# MucDuino_Strawberry.net
KiCad netlist of a schematic drawn in EAGLE
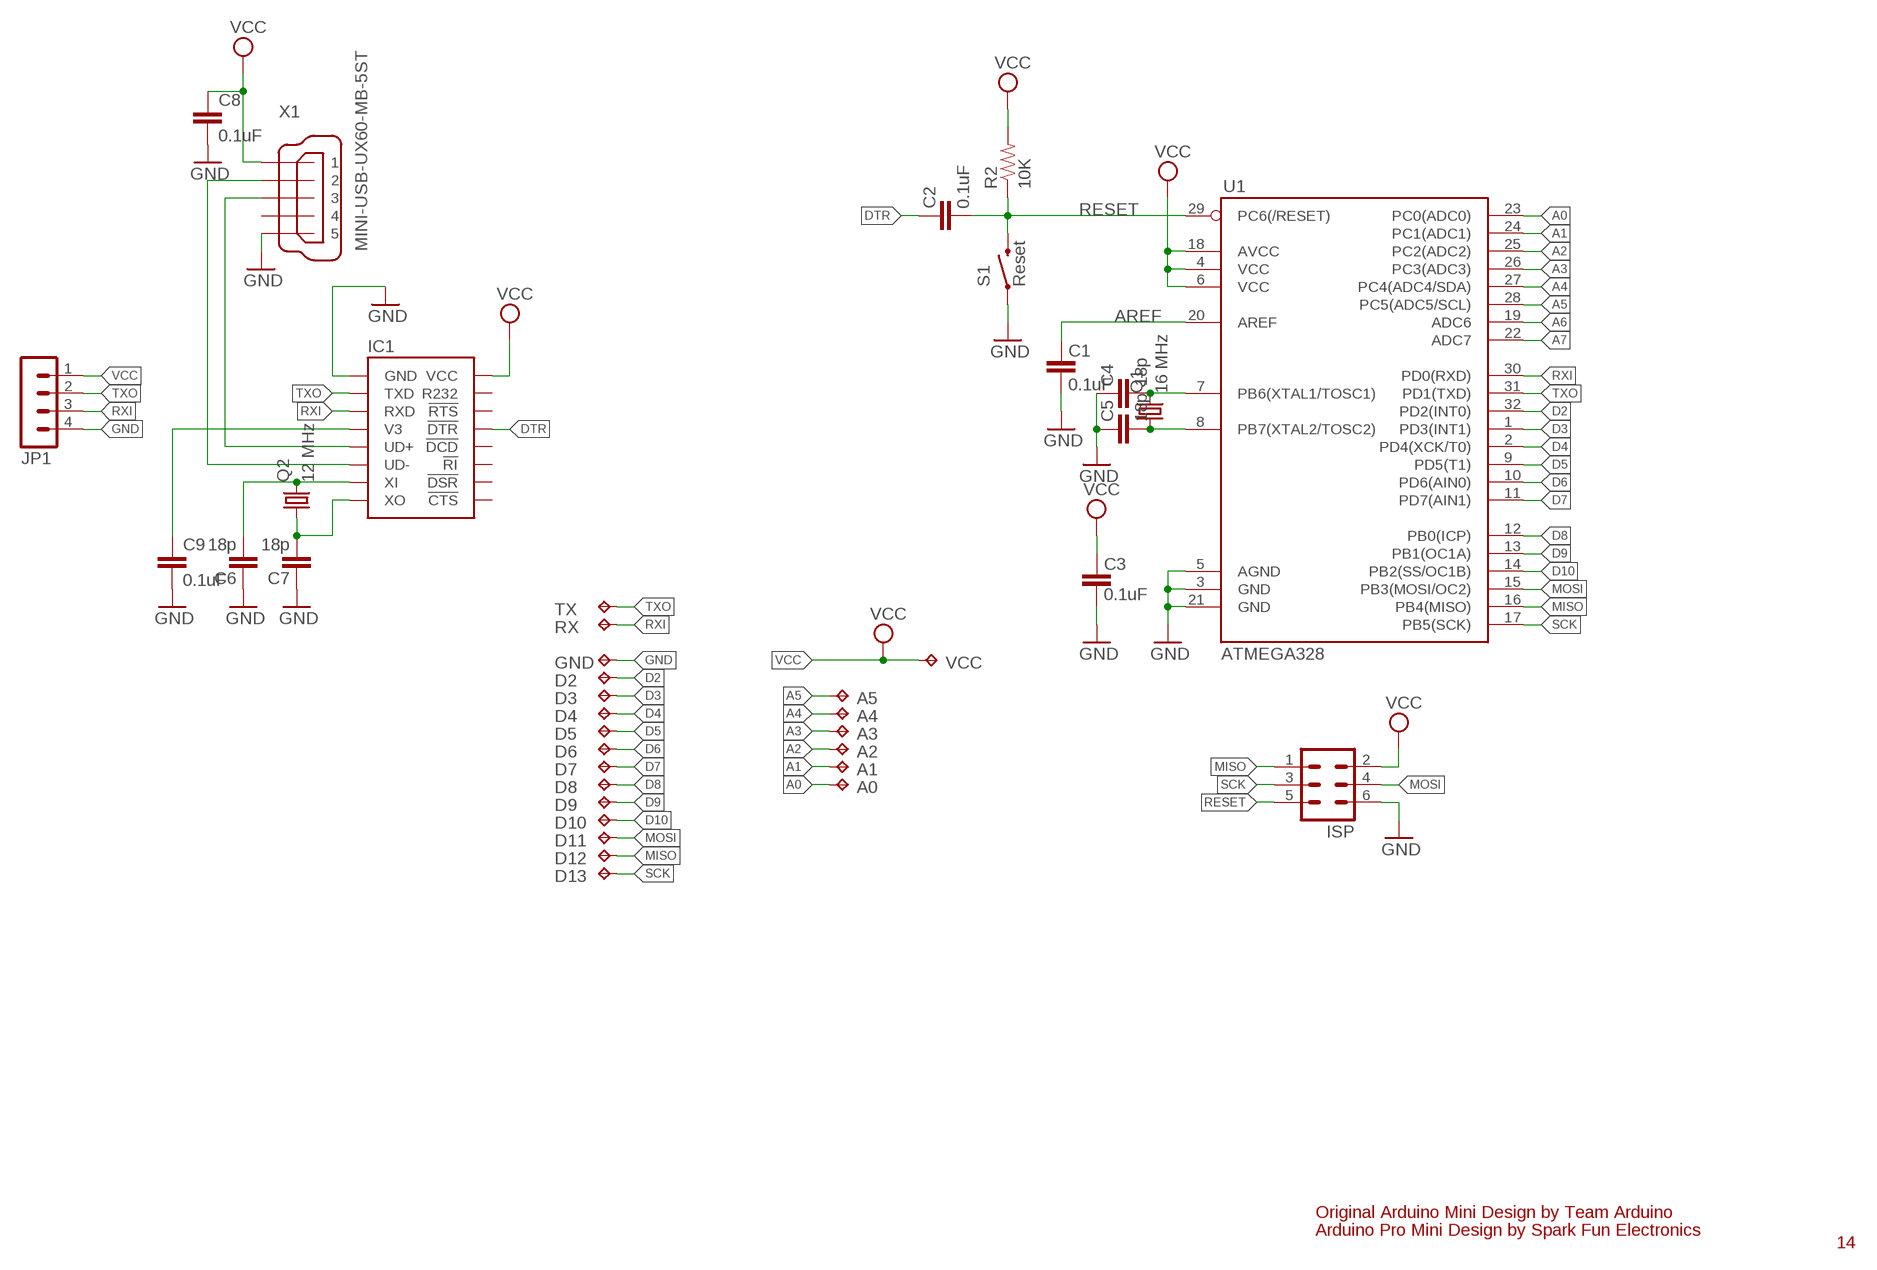
[diagram p0: schematic, sheet 1]

(export (version "E")
  (design (tool "Eeschema 10.0.6"))
  (components
    (comp (ref "A0")
      (value "TPPAD1-13")
      (footprint "eagle-import:P1-13")
      (libsource (lib "eagle-import") (part "TPPAD1-13"))
    )
    (comp (ref "A1")
      (value "TPPAD1-13")
      (footprint "eagle-import:P1-13")
      (libsource (lib "eagle-import") (part "TPPAD1-13"))
    )
    (comp (ref "A2")
      (value "TPPAD1-13")
      (footprint "eagle-import:P1-13")
      (libsource (lib "eagle-import") (part "TPPAD1-13"))
    )
    (comp (ref "A3")
      (value "TPPAD1-13")
      (footprint "eagle-import:P1-13")
      (libsource (lib "eagle-import") (part "TPPAD1-13"))
    )
    (comp (ref "A4")
      (value "TPPAD1-13")
      (footprint "eagle-import:P1-13")
      (libsource (lib "eagle-import") (part "TPPAD1-13"))
    )
    (comp (ref "A5")
      (value "TPPAD1-13")
      (footprint "eagle-import:P1-13")
      (libsource (lib "eagle-import") (part "TPPAD1-13"))
    )
    (comp (ref "C1")
      (value "0.1uF")
      (footprint "eagle-import:0603-CAP")
      (libsource (lib "eagle-import") (part "CAP0603-CAP"))
    )
    (comp (ref "C2")
      (value "0.1uF")
      (footprint "eagle-import:0603-CAP")
      (libsource (lib "eagle-import") (part "CAP0603-CAP"))
    )
    (comp (ref "C3")
      (value "0.1uF")
      (footprint "eagle-import:0603-CAP")
      (libsource (lib "eagle-import") (part "CAP0603-CAP"))
    )
    (comp (ref "C4")
      (value "18p")
      (footprint "eagle-import:0603-CAP")
      (libsource (lib "eagle-import") (part "CAP0603-CAP"))
    )
    (comp (ref "C5")
      (value "18p")
      (footprint "eagle-import:0603-CAP")
      (libsource (lib "eagle-import") (part "CAP0603-CAP"))
    )
    (comp (ref "C6")
      (value "18p")
      (footprint "eagle-import:0603-CAP")
      (libsource (lib "eagle-import") (part "CAP0603-CAP"))
    )
    (comp (ref "C7")
      (value "18p")
      (footprint "eagle-import:0603-CAP")
      (libsource (lib "eagle-import") (part "CAP0603-CAP"))
    )
    (comp (ref "C8")
      (value "0.1uF")
      (footprint "eagle-import:0603-CAP")
      (libsource (lib "eagle-import") (part "CAP0603-CAP"))
    )
    (comp (ref "C9")
      (value "0.1uF")
      (footprint "eagle-import:0603-CAP")
      (libsource (lib "eagle-import") (part "CAP0603-CAP"))
    )
    (comp (ref "D2")
      (value "TPPAD1-13")
      (footprint "eagle-import:P1-13")
      (libsource (lib "eagle-import") (part "TPPAD1-13"))
    )
    (comp (ref "D3")
      (value "TPPAD1-13")
      (footprint "eagle-import:P1-13")
      (libsource (lib "eagle-import") (part "TPPAD1-13"))
    )
    (comp (ref "D4")
      (value "TPPAD1-13")
      (footprint "eagle-import:P1-13")
      (libsource (lib "eagle-import") (part "TPPAD1-13"))
    )
    (comp (ref "D5")
      (value "TPPAD1-13")
      (footprint "eagle-import:P1-13")
      (libsource (lib "eagle-import") (part "TPPAD1-13"))
    )
    (comp (ref "D6")
      (value "TPPAD1-13")
      (footprint "eagle-import:P1-13")
      (libsource (lib "eagle-import") (part "TPPAD1-13"))
    )
    (comp (ref "D7")
      (value "TPPAD1-13")
      (footprint "eagle-import:P1-13")
      (libsource (lib "eagle-import") (part "TPPAD1-13"))
    )
    (comp (ref "D8")
      (value "TPPAD1-13")
      (footprint "eagle-import:P1-13")
      (libsource (lib "eagle-import") (part "TPPAD1-13"))
    )
    (comp (ref "D9")
      (value "TPPAD1-13")
      (footprint "eagle-import:P1-13")
      (libsource (lib "eagle-import") (part "TPPAD1-13"))
    )
    (comp (ref "D10")
      (value "TPPAD1-13")
      (footprint "eagle-import:P1-13")
      (libsource (lib "eagle-import") (part "TPPAD1-13"))
    )
    (comp (ref "D11")
      (value "TPPAD1-13")
      (footprint "eagle-import:P1-13")
      (libsource (lib "eagle-import") (part "TPPAD1-13"))
    )
    (comp (ref "D12")
      (value "TPPAD1-13")
      (footprint "eagle-import:P1-13")
      (libsource (lib "eagle-import") (part "TPPAD1-13"))
    )
    (comp (ref "D13")
      (value "TPPAD1-13")
      (footprint "eagle-import:P1-13")
      (libsource (lib "eagle-import") (part "TPPAD1-13"))
    )
    (comp (ref "GND")
      (value "TPPAD1-13")
      (footprint "eagle-import:P1-13")
      (libsource (lib "eagle-import") (part "TPPAD1-13"))
    )
    (comp (ref "IC1")
      (value "CH340G")
      (footprint "eagle-import:SOP16-209MM")
      (libsource (lib "eagle-import") (part "CH340G"))
    )
    (comp (ref "ISP")
      (value "MA03-2")
      (footprint "eagle-import:MA03-2")
      (libsource (lib "eagle-import") (part "MA03-2"))
    )
    (comp (ref "JP1")
      (value "MA04-1")
      (footprint "eagle-import:MA04-1")
      (libsource (lib "eagle-import") (part "MA04-1"))
    )
    (comp (ref "Q1")
      (value "16 MHz")
      (footprint "eagle-import:HC49UP")
      (libsource (lib "eagle-import") (part "CRYSTALHC49UP"))
    )
    (comp (ref "Q2")
      (value "12 MHz")
      (footprint "eagle-import:HC49UP")
      (libsource (lib "eagle-import") (part "CRYSTALHC49UP"))
    )
    (comp (ref "R2")
      (value "10K")
      (footprint "eagle-import:0603-RES")
      (libsource (lib "eagle-import") (part "RESISTOR0603-RES"))
    )
    (comp (ref "RX")
      (value "TPPAD1-13")
      (footprint "eagle-import:P1-13")
      (libsource (lib "eagle-import") (part "TPPAD1-13"))
    )
    (comp (ref "S1")
      (value "Reset")
      (footprint "eagle-import:TACTILE-SWITCH-SMD-ALT01")
      (libsource (lib "eagle-import") (part "SWITCH-MOMENTARY-2SMD-ALT01"))
    )
    (comp (ref "TX")
      (value "TPPAD1-13")
      (footprint "eagle-import:P1-13")
      (libsource (lib "eagle-import") (part "TPPAD1-13"))
    )
    (comp (ref "U1")
      (value "ATMEGA328")
      (footprint "eagle-import:TQFP32-08")
      (libsource (lib "eagle-import") (part "ATMEGA168"))
    )
    (comp (ref "VCC")
      (value "TPPAD1-13")
      (footprint "eagle-import:P1-13")
      (libsource (lib "eagle-import") (part "TPPAD1-13"))
    )
    (comp (ref "X1")
      (value "MINI-USB-UX60-MB-5ST")
      (footprint "eagle-import:UX60-MB-5ST")
      (libsource (lib "eagle-import") (part "MINI-USB-UX60-MB-5ST"))
    )
  )
  (nets
    (net (code "1") (name "/AREF") (class "Default")
      (node (ref "C1") (pin "2") (pinfunction "2_2") (pintype "passive"))
      (node (ref "U1") (pin "20") (pinfunction "AREF_20") (pintype "bidirectional"))
    )
    (net (code "2") (name "A0") (class "Default")
      (node (ref "A0") (pin "TP") (pinfunction "TP_TP") (pintype "input"))
      (node (ref "U1") (pin "23") (pinfunction "PC0(ADC0)_23") (pintype "bidirectional"))
    )
    (net (code "3") (name "A1") (class "Default")
      (node (ref "A1") (pin "TP") (pinfunction "TP_TP") (pintype "input"))
      (node (ref "U1") (pin "24") (pinfunction "PC1(ADC1)_24") (pintype "bidirectional"))
    )
    (net (code "4") (name "A2") (class "Default")
      (node (ref "A2") (pin "TP") (pinfunction "TP_TP") (pintype "input"))
      (node (ref "U1") (pin "25") (pinfunction "PC2(ADC2)_25") (pintype "bidirectional"))
    )
    (net (code "5") (name "A3") (class "Default")
      (node (ref "A3") (pin "TP") (pinfunction "TP_TP") (pintype "input"))
      (node (ref "U1") (pin "26") (pinfunction "PC3(ADC3)_26") (pintype "bidirectional"))
    )
    (net (code "6") (name "A4") (class "Default")
      (node (ref "A4") (pin "TP") (pinfunction "TP_TP") (pintype "input"))
      (node (ref "U1") (pin "27") (pinfunction "PC4(ADC4/SDA)_27") (pintype "bidirectional"))
    )
    (net (code "7") (name "A5") (class "Default")
      (node (ref "A5") (pin "TP") (pinfunction "TP_TP") (pintype "input"))
      (node (ref "U1") (pin "28") (pinfunction "PC5(ADC5/SCL)_28") (pintype "bidirectional"))
    )
    (net (code "8") (name "A6") (class "Default")
      (node (ref "U1") (pin "19") (pinfunction "ADC6_19") (pintype "bidirectional"))
    )
    (net (code "9") (name "A7") (class "Default")
      (node (ref "U1") (pin "22") (pinfunction "ADC7_22") (pintype "bidirectional"))
    )
    (net (code "10") (name "D2") (class "Default")
      (node (ref "D2") (pin "TP") (pinfunction "TP_TP") (pintype "input"))
      (node (ref "U1") (pin "32") (pinfunction "PD2(INT0)_32") (pintype "bidirectional"))
    )
    (net (code "11") (name "D3") (class "Default")
      (node (ref "D3") (pin "TP") (pinfunction "TP_TP") (pintype "input"))
      (node (ref "U1") (pin "1") (pinfunction "PD3(INT1)_1") (pintype "bidirectional"))
    )
    (net (code "12") (name "D4") (class "Default")
      (node (ref "D4") (pin "TP") (pinfunction "TP_TP") (pintype "input"))
      (node (ref "U1") (pin "2") (pinfunction "PD4(XCK/T0)_2") (pintype "bidirectional"))
    )
    (net (code "13") (name "D5") (class "Default")
      (node (ref "D5") (pin "TP") (pinfunction "TP_TP") (pintype "input"))
      (node (ref "U1") (pin "9") (pinfunction "PD5(T1)_9") (pintype "bidirectional"))
    )
    (net (code "14") (name "D6") (class "Default")
      (node (ref "D6") (pin "TP") (pinfunction "TP_TP") (pintype "input"))
      (node (ref "U1") (pin "10") (pinfunction "PD6(AIN0)_10") (pintype "bidirectional"))
    )
    (net (code "15") (name "D7") (class "Default")
      (node (ref "D7") (pin "TP") (pinfunction "TP_TP") (pintype "input"))
      (node (ref "U1") (pin "11") (pinfunction "PD7(AIN1)_11") (pintype "bidirectional"))
    )
    (net (code "16") (name "D8") (class "Default")
      (node (ref "D8") (pin "TP") (pinfunction "TP_TP") (pintype "input"))
      (node (ref "U1") (pin "12") (pinfunction "PB0(ICP)_12") (pintype "bidirectional"))
    )
    (net (code "17") (name "D9") (class "Default")
      (node (ref "D9") (pin "TP") (pinfunction "TP_TP") (pintype "input"))
      (node (ref "U1") (pin "13") (pinfunction "PB1(OC1A)_13") (pintype "bidirectional"))
    )
    (net (code "18") (name "D10") (class "Default")
      (node (ref "D10") (pin "TP") (pinfunction "TP_TP") (pintype "input"))
      (node (ref "U1") (pin "14") (pinfunction "PB2(SS/OC1B)_14") (pintype "bidirectional"))
    )
    (net (code "19") (name "DTR") (class "Default")
      (node (ref "C2") (pin "2") (pinfunction "2_2") (pintype "passive"))
      (node (ref "IC1") (pin "P$13") (pinfunction "~{DTR}_P$13") (pintype "bidirectional"))
    )
    (net (code "20") (name "GND") (class "Default")
      (node (ref "C1") (pin "1") (pinfunction "1_1") (pintype "passive"))
      (node (ref "C3") (pin "1") (pinfunction "1_1") (pintype "passive"))
      (node (ref "C4") (pin "2") (pinfunction "2_2") (pintype "passive"))
      (node (ref "C5") (pin "2") (pinfunction "2_2") (pintype "passive"))
      (node (ref "C6") (pin "2") (pinfunction "2_2") (pintype "passive"))
      (node (ref "C7") (pin "2") (pinfunction "2_2") (pintype "passive"))
      (node (ref "C8") (pin "2") (pinfunction "2_2") (pintype "passive"))
      (node (ref "C9") (pin "2") (pinfunction "2_2") (pintype "passive"))
      (node (ref "GND") (pin "TP") (pinfunction "TP_TP") (pintype "input"))
      (node (ref "IC1") (pin "P$1") (pinfunction "GND_P$1") (pintype "bidirectional"))
      (node (ref "ISP") (pin "6") (pinfunction "6_6") (pintype "passive"))
      (node (ref "JP1") (pin "4") (pinfunction "4_4") (pintype "passive"))
      (node (ref "S1") (pin "1") (pinfunction "1_1") (pintype "passive"))
      (node (ref "S1") (pin "2") (pinfunction "1_2") (pintype "passive"))
      (node (ref "U1") (pin "21") (pinfunction "GND_21") (pintype "bidirectional"))
      (node (ref "U1") (pin "3") (pinfunction "GND_3") (pintype "bidirectional"))
      (node (ref "U1") (pin "5") (pinfunction "AGND_5") (pintype "bidirectional"))
      (node (ref "X1") (pin "5") (pinfunction "5_5") (pintype "input"))
    )
    (net (code "21") (name "MISO") (class "Default")
      (node (ref "D12") (pin "TP") (pinfunction "TP_TP") (pintype "input"))
      (node (ref "ISP") (pin "1") (pinfunction "1_1") (pintype "passive"))
      (node (ref "U1") (pin "16") (pinfunction "PB4(MISO)_16") (pintype "bidirectional"))
    )
    (net (code "22") (name "MOSI") (class "Default")
      (node (ref "D11") (pin "TP") (pinfunction "TP_TP") (pintype "input"))
      (node (ref "ISP") (pin "4") (pinfunction "4_4") (pintype "passive"))
      (node (ref "U1") (pin "15") (pinfunction "PB3(MOSI/OC2)_15") (pintype "bidirectional"))
    )
    (net (code "23") (name "Net-(IC1-UD+)") (class "Default")
      (node (ref "IC1") (pin "P$5") (pinfunction "UD+_P$5") (pintype "bidirectional"))
      (node (ref "X1") (pin "3") (pinfunction "3_3") (pintype "input"))
    )
    (net (code "24") (name "Net-(IC1-UD-)") (class "Default")
      (node (ref "IC1") (pin "P$6") (pinfunction "UD-_P$6") (pintype "bidirectional"))
      (node (ref "X1") (pin "2") (pinfunction "2_2") (pintype "input"))
    )
    (net (code "25") (name "Net-(IC1-V3)") (class "Default")
      (node (ref "C9") (pin "1") (pinfunction "1_1") (pintype "passive"))
      (node (ref "IC1") (pin "P$4") (pinfunction "V3_P$4") (pintype "bidirectional"))
    )
    (net (code "26") (name "Net-(IC1-XI)") (class "Default")
      (node (ref "C6") (pin "1") (pinfunction "1_1") (pintype "passive"))
      (node (ref "IC1") (pin "P$7") (pinfunction "XI_P$7") (pintype "bidirectional"))
      (node (ref "Q2") (pin "2") (pinfunction "2_2") (pintype "passive"))
    )
    (net (code "27") (name "Net-(IC1-XO)") (class "Default")
      (node (ref "C7") (pin "1") (pinfunction "1_1") (pintype "passive"))
      (node (ref "IC1") (pin "P$8") (pinfunction "XO_P$8") (pintype "bidirectional"))
      (node (ref "Q2") (pin "1") (pinfunction "1_1") (pintype "passive"))
    )
    (net (code "28") (name "Net-(U1-PB6(XTAL1{slash}TOSC1))") (class "Default")
      (node (ref "C4") (pin "1") (pinfunction "1_1") (pintype "passive"))
      (node (ref "Q1") (pin "2") (pinfunction "2_2") (pintype "passive"))
      (node (ref "U1") (pin "7") (pinfunction "PB6(XTAL1/TOSC1)_7") (pintype "bidirectional"))
    )
    (net (code "29") (name "Net-(U1-PB7(XTAL2{slash}TOSC2))") (class "Default")
      (node (ref "C5") (pin "1") (pinfunction "1_1") (pintype "passive"))
      (node (ref "Q1") (pin "1") (pinfunction "1_1") (pintype "passive"))
      (node (ref "U1") (pin "8") (pinfunction "PB7(XTAL2/TOSC2)_8") (pintype "bidirectional"))
    )
    (net (code "30") (name "RESET") (class "Default")
      (node (ref "C2") (pin "1") (pinfunction "1_1") (pintype "passive"))
      (node (ref "ISP") (pin "5") (pinfunction "5_5") (pintype "passive"))
      (node (ref "R2") (pin "1") (pinfunction "1_1") (pintype "passive"))
      (node (ref "S1") (pin "3") (pinfunction "2_3") (pintype "passive"))
      (node (ref "S1") (pin "4") (pinfunction "2_4") (pintype "passive"))
      (node (ref "U1") (pin "29") (pinfunction "PC6(/RESET)_29") (pintype "bidirectional"))
    )
    (net (code "31") (name "RXI") (class "Default")
      (node (ref "IC1") (pin "P$3") (pinfunction "RXD_P$3") (pintype "bidirectional"))
      (node (ref "JP1") (pin "3") (pinfunction "3_3") (pintype "passive"))
      (node (ref "RX") (pin "TP") (pinfunction "TP_TP") (pintype "input"))
      (node (ref "U1") (pin "30") (pinfunction "PD0(RXD)_30") (pintype "bidirectional"))
    )
    (net (code "32") (name "SCK") (class "Default")
      (node (ref "D13") (pin "TP") (pinfunction "TP_TP") (pintype "input"))
      (node (ref "ISP") (pin "3") (pinfunction "3_3") (pintype "passive"))
      (node (ref "U1") (pin "17") (pinfunction "PB5(SCK)_17") (pintype "bidirectional"))
    )
    (net (code "33") (name "TXO") (class "Default")
      (node (ref "IC1") (pin "P$2") (pinfunction "TXD_P$2") (pintype "bidirectional"))
      (node (ref "JP1") (pin "2") (pinfunction "2_2") (pintype "passive"))
      (node (ref "TX") (pin "TP") (pinfunction "TP_TP") (pintype "input"))
      (node (ref "U1") (pin "31") (pinfunction "PD1(TXD)_31") (pintype "bidirectional"))
    )
    (net (code "34") (name "VCC") (class "Default")
      (node (ref "C3") (pin "2") (pinfunction "2_2") (pintype "passive"))
      (node (ref "C8") (pin "1") (pinfunction "1_1") (pintype "passive"))
      (node (ref "IC1") (pin "P$16") (pinfunction "VCC_P$16") (pintype "bidirectional"))
      (node (ref "ISP") (pin "2") (pinfunction "2_2") (pintype "passive"))
      (node (ref "JP1") (pin "1") (pinfunction "1_1") (pintype "passive"))
      (node (ref "R2") (pin "2") (pinfunction "2_2") (pintype "passive"))
      (node (ref "U1") (pin "18") (pinfunction "AVCC_18") (pintype "bidirectional"))
      (node (ref "U1") (pin "4") (pinfunction "VCC_4") (pintype "bidirectional"))
      (node (ref "U1") (pin "6") (pinfunction "VCC_6") (pintype "bidirectional"))
      (node (ref "VCC") (pin "TP") (pinfunction "TP_TP") (pintype "input"))
      (node (ref "X1") (pin "1") (pinfunction "1_1") (pintype "input"))
    )
    (net (code "35") (name "unconnected-(IC1-R232-PadP$15)") (class "Default")
      (node (ref "IC1") (pin "P$15") (pinfunction "R232_P$15") (pintype "bidirectional"))
    )
    (net (code "36") (name "unconnected-(IC1-~{CTS}-PadP$9)") (class "Default")
      (node (ref "IC1") (pin "P$9") (pinfunction "~{CTS}_P$9") (pintype "bidirectional"))
    )
    (net (code "37") (name "unconnected-(IC1-~{DCD}-PadP$12)") (class "Default")
      (node (ref "IC1") (pin "P$12") (pinfunction "~{DCD}_P$12") (pintype "bidirectional"))
    )
    (net (code "38") (name "unconnected-(IC1-~{DSR}-PadP$10)") (class "Default")
      (node (ref "IC1") (pin "P$10") (pinfunction "~{DSR}_P$10") (pintype "bidirectional"))
    )
    (net (code "39") (name "unconnected-(IC1-~{RI}-PadP$11)") (class "Default")
      (node (ref "IC1") (pin "P$11") (pinfunction "~{RI}_P$11") (pintype "bidirectional"))
    )
    (net (code "40") (name "unconnected-(IC1-~{RTS}-PadP$14)") (class "Default")
      (node (ref "IC1") (pin "P$14") (pinfunction "~{RTS}_P$14") (pintype "bidirectional"))
    )
    (net (code "41") (name "unconnected-(X1-Pad4)") (class "Default")
      (node (ref "X1") (pin "4") (pinfunction "4_4") (pintype "input"))
    )
  )
)
